# Hall_Effect.net
KiCad netlist of a schematic drawn in Altium Designer
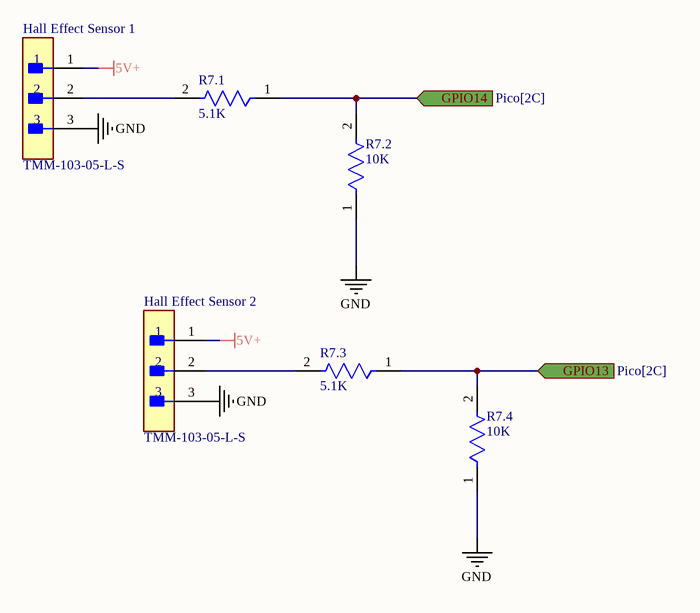
[diagram p0: Hall Effect.SchDoc]

(export (version "E")
  (design (tool "Eeschema 10.0.6"))
  (components
    (comp (ref "Hall Effect Sensor 1")
      (value "TMM-103-05-L-S")
      (footprint "FP-TMM-103-05-L-S-MFG")
      (description "2MM TERMINAL STRIP")
      (libsource (lib "Altium Content Vault") (part "0d3f023dd272f625e17a2be33dea85f"))
    )
    (comp (ref "Hall Effect Sensor 2")
      (value "TMM-103-05-L-S")
      (footprint "FP-TMM-103-05-L-S-MFG")
      (description "2MM TERMINAL STRIP")
      (libsource (lib "Altium Content Vault") (part "0d3f023dd272f625e17a2be33dea85f"))
    )
    (comp (ref "R7.1")
      (value "5.1K")
      (footprint "FP-MFR-12-MFG")
      (description "RES MF 1/6W 1% AXIAL")
      (fields (field (name "TOLERANCE") "1%"))
      (libsource (lib "Altium Content Vault") (part "1029c3af85768c4190bb7ad29bc67b5"))
    )
    (comp (ref "R7.2")
      (value "10K")
      (footprint "FP-MFR-12-MFG")
      (description "RES MF 1/6W 1% AXIAL")
      (fields (field (name "TOLERANCE") "1%"))
      (libsource (lib "Altium Content Vault") (part "1029c3af85768c4190bb7ad29bc67b5"))
    )
    (comp (ref "R7.3")
      (value "5.1K")
      (footprint "FP-MFR-12-MFG")
      (description "RES MF 1/6W 1% AXIAL")
      (fields (field (name "TOLERANCE") "1%"))
      (libsource (lib "Altium Content Vault") (part "1029c3af85768c4190bb7ad29bc67b5"))
    )
    (comp (ref "R7.4")
      (value "10K")
      (footprint "FP-MFR-12-MFG")
      (description "RES MF 1/6W 1% AXIAL")
      (fields (field (name "TOLERANCE") "1%"))
      (libsource (lib "Altium Content Vault") (part "1029c3af85768c4190bb7ad29bc67b5"))
    )
  )
  (nets
    (net (code "1") (name "/GPIO13") (class "Default")
      (node (ref "R7.3") (pin "1") (pinfunction "1_1") (pintype "passive"))
      (node (ref "R7.4") (pin "2") (pinfunction "2_2") (pintype "passive"))
    )
    (net (code "2") (name "/GPIO14") (class "Default")
      (node (ref "R7.1") (pin "1") (pinfunction "1_1") (pintype "passive"))
      (node (ref "R7.2") (pin "2") (pinfunction "2_2") (pintype "passive"))
    )
    (net (code "3") (name "5V+") (class "Default")
      (node (ref "Hall Effect Sensor 1") (pin "1") (pinfunction "1_1") (pintype "passive"))
      (node (ref "Hall Effect Sensor 2") (pin "1") (pinfunction "1_1") (pintype "passive"))
    )
    (net (code "4") (name "GND") (class "Default")
      (node (ref "Hall Effect Sensor 1") (pin "3") (pinfunction "3_3") (pintype "passive"))
      (node (ref "Hall Effect Sensor 2") (pin "3") (pinfunction "3_3") (pintype "passive"))
      (node (ref "R7.2") (pin "1") (pinfunction "1_1") (pintype "passive"))
      (node (ref "R7.4") (pin "1") (pinfunction "1_1") (pintype "passive"))
    )
    (net (code "5") (name "Net-(Hall Effect Sensor 1-Pad2)") (class "Default")
      (node (ref "Hall Effect Sensor 1") (pin "2") (pinfunction "2_2") (pintype "passive"))
      (node (ref "R7.1") (pin "2") (pinfunction "2_2") (pintype "passive"))
    )
    (net (code "6") (name "Net-(Hall Effect Sensor 2-Pad2)") (class "Default")
      (node (ref "Hall Effect Sensor 2") (pin "2") (pinfunction "2_2") (pintype "passive"))
      (node (ref "R7.3") (pin "2") (pinfunction "2_2") (pintype "passive"))
    )
  )
)
